# Kasli-SOC_bank502_DDR.net
KiCad netlist of a schematic drawn in Altium Designer
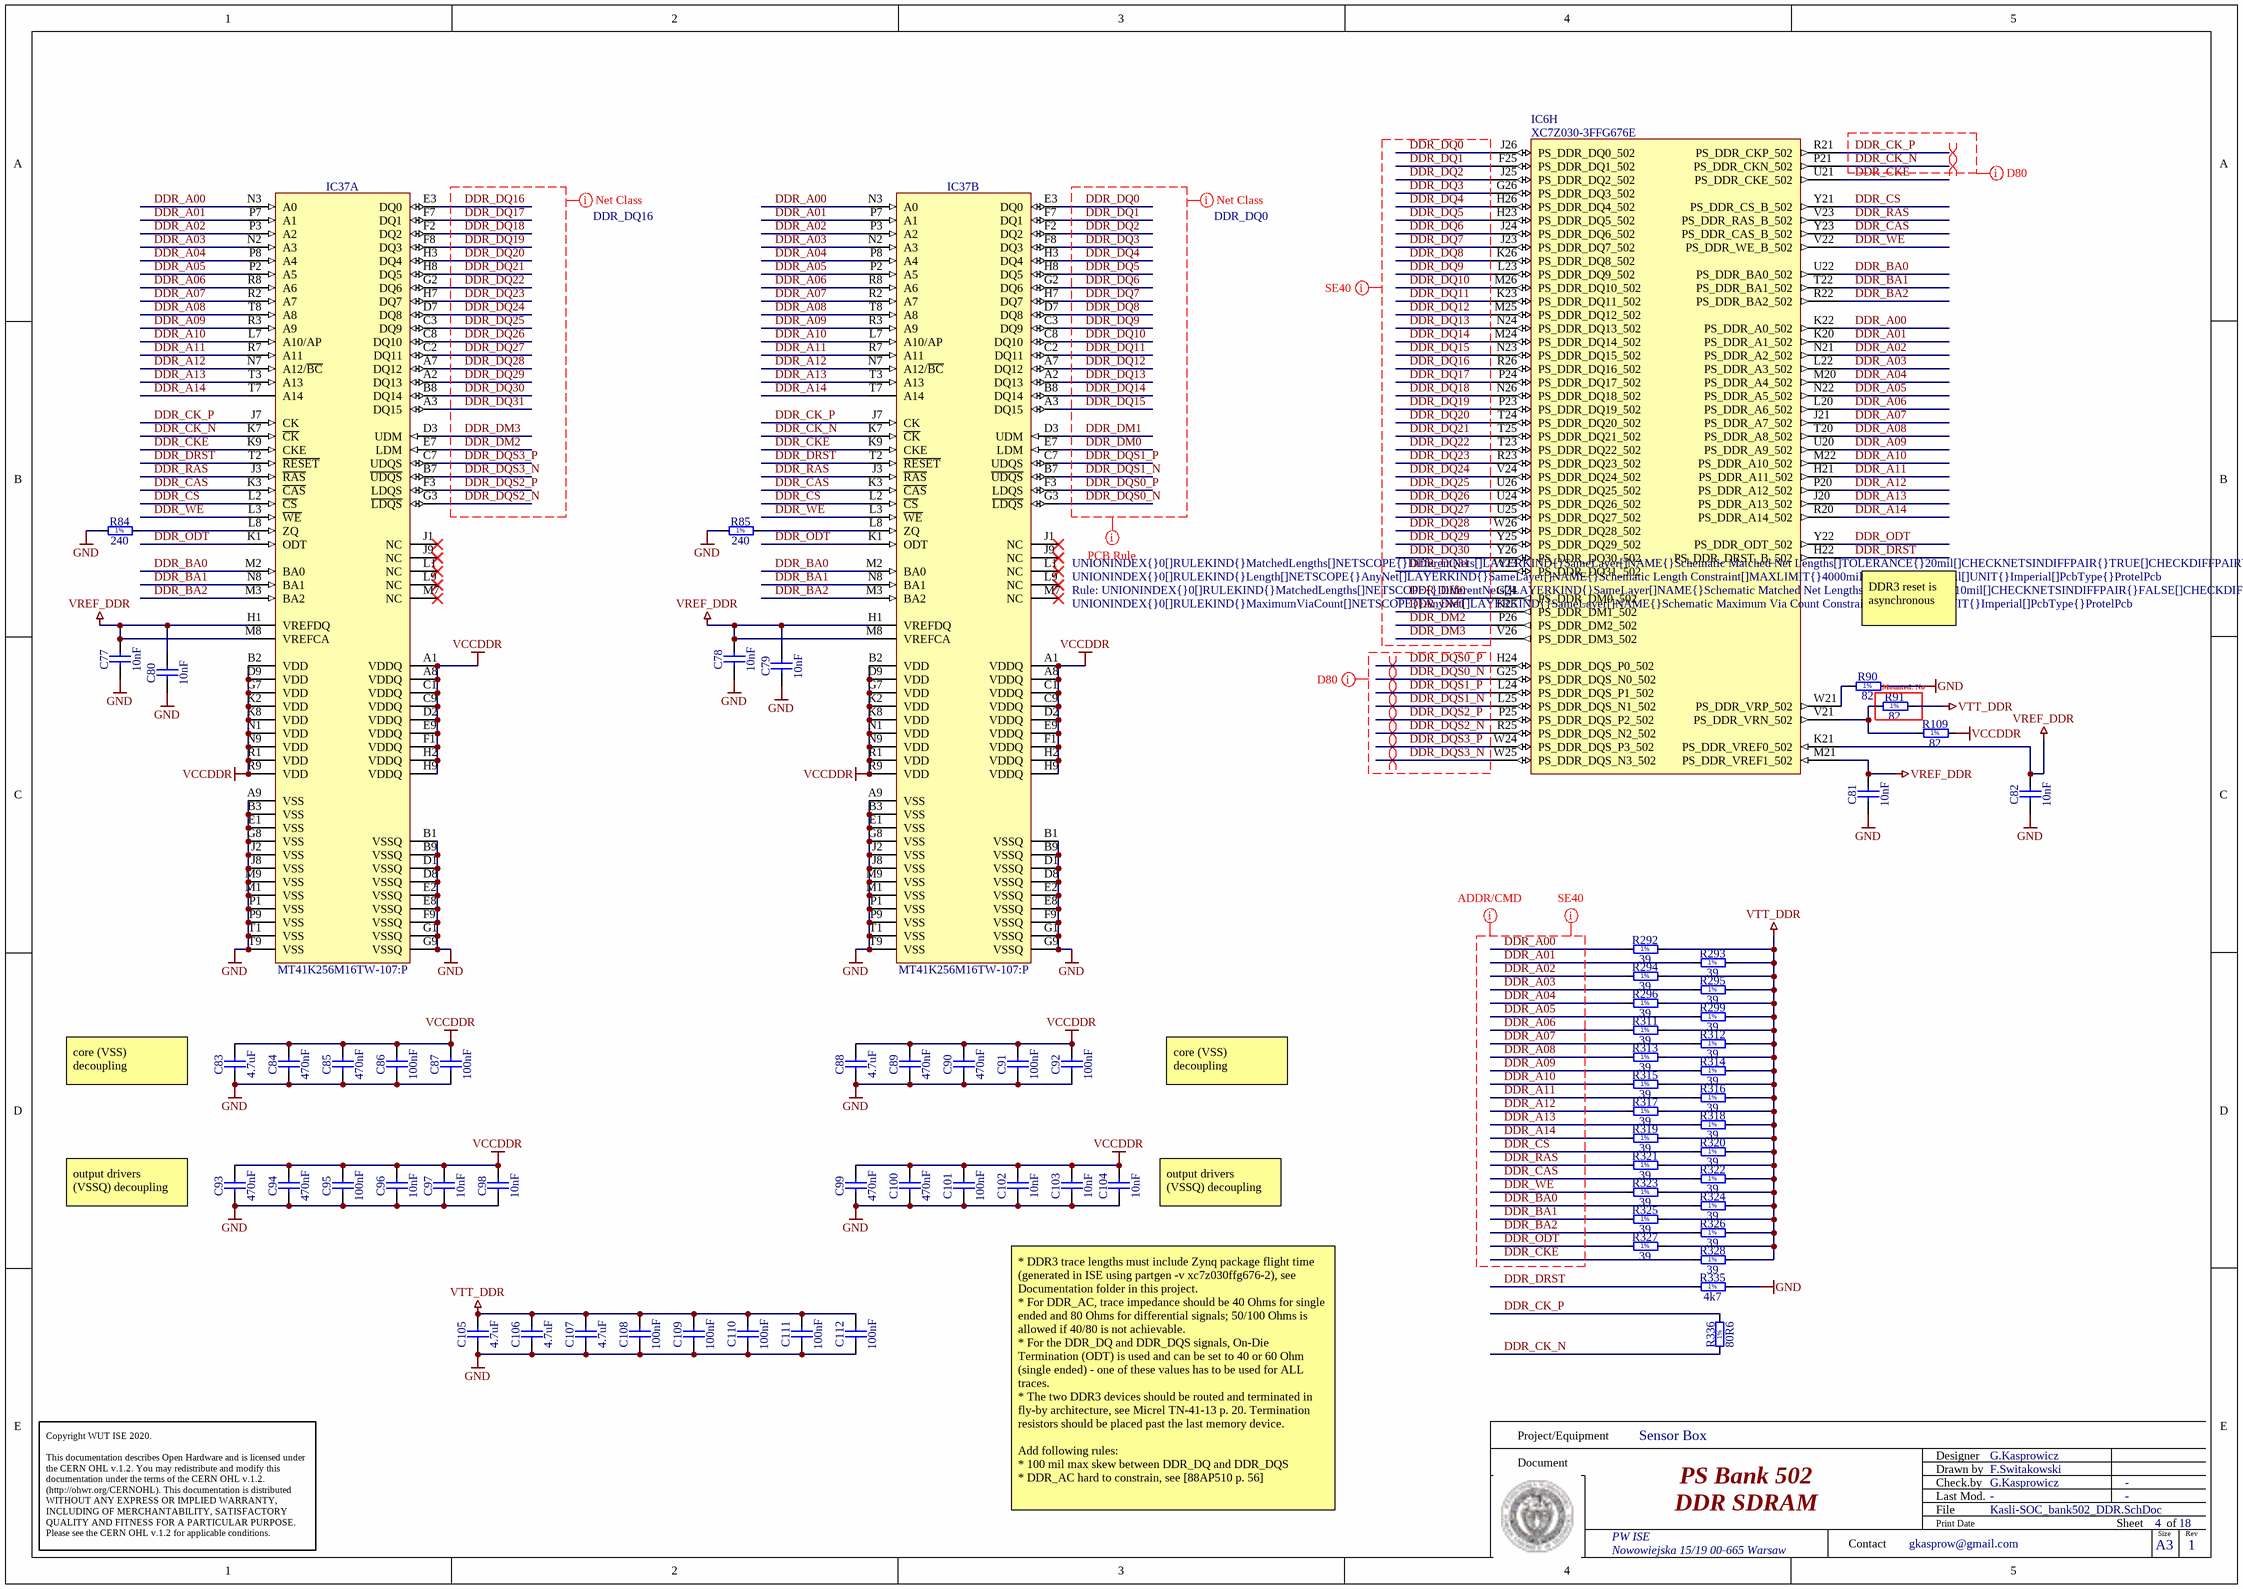
[diagram p0: Kasli-SOC_bank502_DDR.SchDoc]

(export (version "E")
  (design (tool "Eeschema 10.0.6"))
  (components
    (comp (ref "C77")
      (value "10nF")
      (footprint "CAPC1005X55N")
      (description "Non-polarised capacitor")
      (fields
        (field (name "PART NUMBER") "CC0402_10NF_16V_10%_X7R")
        (field (name "VOLTAGE") "16V")
        (field (name "AUTHOR") "CERN DEM JLC")
      )
      (libsource (lib "Capacitors") (part "Capacitor - non polarized"))
    )
    (comp (ref "C78")
      (value "10nF")
      (footprint "CAPC1005X55N")
      (description "Non-polarised capacitor")
      (fields
        (field (name "PART NUMBER") "CC0402_10NF_16V_10%_X7R")
        (field (name "VOLTAGE") "16V")
        (field (name "AUTHOR") "CERN DEM JLC")
      )
      (libsource (lib "Capacitors") (part "Capacitor - non polarized"))
    )
    (comp (ref "C79")
      (value "10nF")
      (footprint "CAPC1005X55N")
      (description "Non-polarised capacitor")
      (fields
        (field (name "PART NUMBER") "CC0402_10NF_16V_10%_X7R")
        (field (name "VOLTAGE") "16V")
        (field (name "AUTHOR") "CERN DEM JLC")
      )
      (libsource (lib "Capacitors") (part "Capacitor - non polarized"))
    )
    (comp (ref "C80")
      (value "10nF")
      (footprint "CAPC1005X55N")
      (description "Non-polarised capacitor")
      (fields
        (field (name "PART NUMBER") "CC0402_10NF_16V_10%_X7R")
        (field (name "VOLTAGE") "16V")
        (field (name "AUTHOR") "CERN DEM JLC")
      )
      (libsource (lib "Capacitors") (part "Capacitor - non polarized"))
    )
    (comp (ref "C81")
      (value "10nF")
      (footprint "CAPC0603X33N")
      (description "Non-polarised capacitor")
      (fields
        (field (name "PART NUMBER") "CC0201_10NF_10V_10%_X5R")
        (field (name "VOLTAGE") "10V")
        (field (name "AUTHOR") "CERN DEM JLC")
      )
      (libsource (lib "Capacitors") (part "Capacitor - non polarized"))
    )
    (comp (ref "C82")
      (value "10nF")
      (footprint "CAPC0603X33N")
      (description "Non-polarised capacitor")
      (fields
        (field (name "PART NUMBER") "CC0201_10NF_10V_10%_X5R")
        (field (name "VOLTAGE") "10V")
        (field (name "AUTHOR") "CERN DEM JLC")
      )
      (libsource (lib "Capacitors") (part "Capacitor - non polarized"))
    )
    (comp (ref "C83")
      (value "4.7uF")
      (footprint "CAPC1005X55N")
      (description "Non-polarised capacitor")
      (fields
        (field (name "PART NUMBER") "CC0402_4.7UF_6.3V_20%_X5R")
        (field (name "VOLTAGE") "6.3V")
        (field (name "AUTHOR") "CERN DEM JLC")
      )
      (libsource (lib "Capacitors") (part "Capacitor - non polarized"))
    )
    (comp (ref "C84")
      (value "470nF")
      (footprint "CAPC1005X55N")
      (description "Non-polarised capacitor")
      (fields
        (field (name "PART NUMBER") "CC0402_470NF_16V_10%_X5R")
        (field (name "VOLTAGE") "16V")
        (field (name "AUTHOR") "CERN DEM JLC")
      )
      (libsource (lib "Capacitors") (part "Capacitor - non polarized"))
    )
    (comp (ref "C85")
      (value "470nF")
      (footprint "CAPC1005X55N")
      (description "Non-polarised capacitor")
      (fields
        (field (name "PART NUMBER") "CC0402_470NF_16V_10%_X5R")
        (field (name "VOLTAGE") "16V")
        (field (name "AUTHOR") "CERN DEM JLC")
      )
      (libsource (lib "Capacitors") (part "Capacitor - non polarized"))
    )
    (comp (ref "C86")
      (value "100nF")
      (footprint "CAPC1005X55N")
      (description "Non-polarised capacitor")
      (fields
        (field (name "PART NUMBER") "CC0402_100NF_16V_10%_X7R")
        (field (name "VOLTAGE") "16V")
        (field (name "AUTHOR") "CERN DEM JLC")
      )
      (libsource (lib "Capacitors") (part "Capacitor - non polarized"))
    )
    (comp (ref "C87")
      (value "100nF")
      (footprint "CAPC1005X55N")
      (description "Non-polarised capacitor")
      (fields
        (field (name "PART NUMBER") "CC0402_100NF_16V_10%_X7R")
        (field (name "VOLTAGE") "16V")
        (field (name "AUTHOR") "CERN DEM JLC")
      )
      (libsource (lib "Capacitors") (part "Capacitor - non polarized"))
    )
    (comp (ref "C88")
      (value "4.7uF")
      (footprint "CAPC1005X55N")
      (description "Non-polarised capacitor")
      (fields
        (field (name "PART NUMBER") "CC0402_4.7UF_6.3V_20%_X5R")
        (field (name "VOLTAGE") "6.3V")
        (field (name "AUTHOR") "CERN DEM JLC")
      )
      (libsource (lib "Capacitors") (part "Capacitor - non polarized"))
    )
    (comp (ref "C89")
      (value "470nF")
      (footprint "CAPC1005X55N")
      (description "Non-polarised capacitor")
      (fields
        (field (name "PART NUMBER") "CC0402_470NF_16V_10%_X5R")
        (field (name "VOLTAGE") "16V")
        (field (name "AUTHOR") "CERN DEM JLC")
      )
      (libsource (lib "Capacitors") (part "Capacitor - non polarized"))
    )
    (comp (ref "C90")
      (value "470nF")
      (footprint "CAPC1005X55N")
      (description "Non-polarised capacitor")
      (fields
        (field (name "PART NUMBER") "CC0402_470NF_16V_10%_X5R")
        (field (name "VOLTAGE") "16V")
        (field (name "AUTHOR") "CERN DEM JLC")
      )
      (libsource (lib "Capacitors") (part "Capacitor - non polarized"))
    )
    (comp (ref "C91")
      (value "100nF")
      (footprint "CAPC1005X55N")
      (description "Non-polarised capacitor")
      (fields
        (field (name "PART NUMBER") "CC0402_100NF_16V_10%_X7R")
        (field (name "VOLTAGE") "16V")
        (field (name "AUTHOR") "CERN DEM JLC")
      )
      (libsource (lib "Capacitors") (part "Capacitor - non polarized"))
    )
    (comp (ref "C92")
      (value "100nF")
      (footprint "CAPC1005X55N")
      (description "Non-polarised capacitor")
      (fields
        (field (name "PART NUMBER") "CC0402_100NF_16V_10%_X7R")
        (field (name "VOLTAGE") "16V")
        (field (name "AUTHOR") "CERN DEM JLC")
      )
      (libsource (lib "Capacitors") (part "Capacitor - non polarized"))
    )
    (comp (ref "C93")
      (value "470nF")
      (footprint "CAPC1005X55N")
      (description "Non-polarised capacitor")
      (fields
        (field (name "PART NUMBER") "CC0402_470NF_16V_10%_X5R")
        (field (name "VOLTAGE") "16V")
        (field (name "AUTHOR") "CERN DEM JLC")
      )
      (libsource (lib "Capacitors") (part "Capacitor - non polarized"))
    )
    (comp (ref "C94")
      (value "470nF")
      (footprint "CAPC1005X55N")
      (description "Non-polarised capacitor")
      (fields
        (field (name "PART NUMBER") "CC0402_470NF_16V_10%_X5R")
        (field (name "VOLTAGE") "16V")
        (field (name "AUTHOR") "CERN DEM JLC")
      )
      (libsource (lib "Capacitors") (part "Capacitor - non polarized"))
    )
    (comp (ref "C95")
      (value "100nF")
      (footprint "CAPC1005X55N")
      (description "Non-polarised capacitor")
      (fields
        (field (name "PART NUMBER") "CC0402_100NF_16V_10%_X7R")
        (field (name "VOLTAGE") "16V")
        (field (name "AUTHOR") "CERN DEM JLC")
      )
      (libsource (lib "Capacitors") (part "Capacitor - non polarized"))
    )
    (comp (ref "C96")
      (value "10nF")
      (footprint "CAPC1005X55N")
      (description "Non-polarised capacitor")
      (fields
        (field (name "PART NUMBER") "CC0402_10NF_16V_10%_X7R")
        (field (name "VOLTAGE") "16V")
        (field (name "AUTHOR") "CERN DEM JLC")
      )
      (libsource (lib "Capacitors") (part "Capacitor - non polarized"))
    )
    (comp (ref "C97")
      (value "10nF")
      (footprint "CAPC1005X55N")
      (description "Non-polarised capacitor")
      (fields
        (field (name "PART NUMBER") "CC0402_10NF_16V_10%_X7R")
        (field (name "VOLTAGE") "16V")
        (field (name "AUTHOR") "CERN DEM JLC")
      )
      (libsource (lib "Capacitors") (part "Capacitor - non polarized"))
    )
    (comp (ref "C98")
      (value "10nF")
      (footprint "CAPC1005X55N")
      (description "Non-polarised capacitor")
      (fields
        (field (name "PART NUMBER") "CC0402_10NF_16V_10%_X7R")
        (field (name "VOLTAGE") "16V")
        (field (name "AUTHOR") "CERN DEM JLC")
      )
      (libsource (lib "Capacitors") (part "Capacitor - non polarized"))
    )
    (comp (ref "C99")
      (value "470nF")
      (footprint "CAPC1005X55N")
      (description "Non-polarised capacitor")
      (fields
        (field (name "PART NUMBER") "CC0402_470NF_16V_10%_X5R")
        (field (name "VOLTAGE") "16V")
        (field (name "AUTHOR") "CERN DEM JLC")
      )
      (libsource (lib "Capacitors") (part "Capacitor - non polarized"))
    )
    (comp (ref "C100")
      (value "470nF")
      (footprint "CAPC1005X55N")
      (description "Non-polarised capacitor")
      (fields
        (field (name "PART NUMBER") "CC0402_470NF_16V_10%_X5R")
        (field (name "VOLTAGE") "16V")
        (field (name "AUTHOR") "CERN DEM JLC")
      )
      (libsource (lib "Capacitors") (part "Capacitor - non polarized"))
    )
    (comp (ref "C101")
      (value "100nF")
      (footprint "CAPC1005X55N")
      (description "Non-polarised capacitor")
      (fields
        (field (name "PART NUMBER") "CC0402_100NF_16V_10%_X7R")
        (field (name "VOLTAGE") "16V")
        (field (name "AUTHOR") "CERN DEM JLC")
      )
      (libsource (lib "Capacitors") (part "Capacitor - non polarized"))
    )
    (comp (ref "C102")
      (value "10nF")
      (footprint "CAPC1005X55N")
      (description "Non-polarised capacitor")
      (fields
        (field (name "PART NUMBER") "CC0402_10NF_16V_10%_X7R")
        (field (name "VOLTAGE") "16V")
        (field (name "AUTHOR") "CERN DEM JLC")
      )
      (libsource (lib "Capacitors") (part "Capacitor - non polarized"))
    )
    (comp (ref "C103")
      (value "10nF")
      (footprint "CAPC1005X55N")
      (description "Non-polarised capacitor")
      (fields
        (field (name "PART NUMBER") "CC0402_10NF_16V_10%_X7R")
        (field (name "VOLTAGE") "16V")
        (field (name "AUTHOR") "CERN DEM JLC")
      )
      (libsource (lib "Capacitors") (part "Capacitor - non polarized"))
    )
    (comp (ref "C104")
      (value "10nF")
      (footprint "CAPC1005X55N")
      (description "Non-polarised capacitor")
      (fields
        (field (name "PART NUMBER") "CC0402_10NF_16V_10%_X7R")
        (field (name "VOLTAGE") "16V")
        (field (name "AUTHOR") "CERN DEM JLC")
      )
      (libsource (lib "Capacitors") (part "Capacitor - non polarized"))
    )
    (comp (ref "C105")
      (value "4.7uF")
      (footprint "CAPC1005X55N")
      (description "Non-polarised capacitor")
      (fields
        (field (name "PART NUMBER") "CC0402_4.7UF_6.3V_20%_X5R")
        (field (name "VOLTAGE") "6.3V")
        (field (name "AUTHOR") "CERN DEM JLC")
      )
      (libsource (lib "Capacitors") (part "Capacitor - non polarized"))
    )
    (comp (ref "C106")
      (value "4.7uF")
      (footprint "CAPC1005X55N")
      (description "Non-polarised capacitor")
      (fields
        (field (name "PART NUMBER") "CC0402_4.7UF_6.3V_20%_X5R")
        (field (name "VOLTAGE") "6.3V")
        (field (name "AUTHOR") "CERN DEM JLC")
      )
      (libsource (lib "Capacitors") (part "Capacitor - non polarized"))
    )
    (comp (ref "C107")
      (value "4.7uF")
      (footprint "CAPC1005X55N")
      (description "Non-polarised capacitor")
      (fields
        (field (name "PART NUMBER") "CC0402_4.7UF_6.3V_20%_X5R")
        (field (name "VOLTAGE") "6.3V")
        (field (name "AUTHOR") "CERN DEM JLC")
      )
      (libsource (lib "Capacitors") (part "Capacitor - non polarized"))
    )
    (comp (ref "C108")
      (value "100nF")
      (footprint "CAPC1005X55N")
      (description "Non-polarised capacitor")
      (fields
        (field (name "PART NUMBER") "CC0402_100NF_16V_10%_X7R")
        (field (name "VOLTAGE") "16V")
        (field (name "AUTHOR") "CERN DEM JLC")
      )
      (libsource (lib "Capacitors") (part "Capacitor - non polarized"))
    )
    (comp (ref "C109")
      (value "100nF")
      (footprint "CAPC1005X55N")
      (description "Non-polarised capacitor")
      (fields
        (field (name "PART NUMBER") "CC0402_100NF_16V_10%_X7R")
        (field (name "VOLTAGE") "16V")
        (field (name "AUTHOR") "CERN DEM JLC")
      )
      (libsource (lib "Capacitors") (part "Capacitor - non polarized"))
    )
    (comp (ref "C110")
      (value "100nF")
      (footprint "CAPC1005X55N")
      (description "Non-polarised capacitor")
      (fields
        (field (name "PART NUMBER") "CC0402_100NF_16V_10%_X7R")
        (field (name "VOLTAGE") "16V")
        (field (name "AUTHOR") "CERN DEM JLC")
      )
      (libsource (lib "Capacitors") (part "Capacitor - non polarized"))
    )
    (comp (ref "C111")
      (value "100nF")
      (footprint "CAPC1005X55N")
      (description "Non-polarised capacitor")
      (fields
        (field (name "PART NUMBER") "CC0402_100NF_16V_10%_X7R")
        (field (name "VOLTAGE") "16V")
        (field (name "AUTHOR") "CERN DEM JLC")
      )
      (libsource (lib "Capacitors") (part "Capacitor - non polarized"))
    )
    (comp (ref "C112")
      (value "100nF")
      (footprint "CAPC1005X55N")
      (description "Non-polarised capacitor")
      (fields
        (field (name "PART NUMBER") "CC0402_100NF_16V_10%_X7R")
        (field (name "VOLTAGE") "16V")
        (field (name "AUTHOR") "CERN DEM JLC")
      )
      (libsource (lib "Capacitors") (part "Capacitor - non polarized"))
    )
    (comp (ref "IC6")
      (value "XC7Z030-3FFG676E")
      (footprint "BGA676C100P26X26_2700X2700X324")
      (fields (field (name "MANUFACTURER") "XILINX") (field (name "AUTHOR") "CERN DEM JLC"))
      (libsource (lib "ICs And Semiconductors") (part "XC7Z030-2FFG676I"))
    )
    (comp (ref "IC37A")
      (value "MT41K256M16TW-107:P")
      (footprint "BGA96C80P9X16_800X1400X120")
      (description "32 Meg x 16 x 8 Banks DDR3L SDRAM")
      (fields (field (name "MANUFACTURER") "MICRON TECHNOLOGY") (field (name "AUTHOR") "CERN DEM MR"))
      (libsource (lib "ICs And Semiconductors") (part "MT41K256M16TW-107{colon}P"))
    )
    (comp (ref "IC37B")
      (value "MT41K256M16TW-107:P")
      (footprint "BGA96C80P9X16_800X1400X120")
      (description "32 Meg x 16 x 8 Banks DDR3L SDRAM")
      (fields (field (name "MANUFACTURER") "MICRON TECHNOLOGY") (field (name "AUTHOR") "CERN DEM MR"))
      (libsource (lib "ICs And Semiconductors") (part "MT41K256M16TW-107{colon}P"))
    )
    (comp (ref "R84")
      (value "240")
      (footprint "RESC1005X40N")
      (description "Resistor - 1%")
      (fields
        (field (name "PART NUMBER") "R0402_240R_1%_0.0625W_100PPM")
        (field (name "POWER") "0.0625W")
        (field (name "AUTHOR") "CERN DEM JLC")
      )
      (libsource (lib "Resistors") (part "Resistor - 1%"))
    )
    (comp (ref "R85")
      (value "240")
      (footprint "RESC1005X40N")
      (description "Resistor - 1%")
      (fields
        (field (name "PART NUMBER") "R0402_240R_1%_0.0625W_100PPM")
        (field (name "POWER") "0.0625W")
        (field (name "AUTHOR") "CERN DEM JLC")
      )
      (libsource (lib "Resistors") (part "Resistor - 1%"))
    )
    (comp (ref "R90")
      (value "82")
      (footprint "RESC1005X40N")
      (description "Resistor - 1%")
      (fields
        (field (name "PART NUMBER") "R0402_82R_1%_0.0625W_100PPM")
        (field (name "POWER") "0.0625W")
        (field (name "AUTHOR") "CERN DEM JLC")
      )
      (libsource (lib "Resistors") (part "Resistor - 1%"))
    )
    (comp (ref "R91")
      (value "82")
      (footprint "RESC1005X40N")
      (description "Resistor - 1%")
      (fields
        (field (name "PART NUMBER") "R0402_82R_1%_0.0625W_100PPM")
        (field (name "POWER") "0.0625W")
        (field (name "AUTHOR") "CERN DEM JLC")
      )
      (libsource (lib "Resistors") (part "Resistor - 1%"))
    )
    (comp (ref "R109")
      (value "82")
      (footprint "RESC1005X40N")
      (description "Resistor - 1%")
      (fields
        (field (name "PART NUMBER") "R0402_82R_1%_0.0625W_100PPM")
        (field (name "POWER") "0.0625W")
        (field (name "AUTHOR") "CERN DEM JLC")
      )
      (libsource (lib "Resistors") (part "Resistor - 1%"))
    )
    (comp (ref "R292")
      (value "39")
      (footprint "RESC1005X40N")
      (description "Resistor - 1%")
      (fields
        (field (name "PART NUMBER") "R0402_39R_1%_0.0625W_100PPM")
        (field (name "POWER") "0.0625W")
        (field (name "AUTHOR") "CERN DEM JLC")
      )
      (libsource (lib "Resistors") (part "Resistor - 1%"))
    )
    (comp (ref "R293")
      (value "39")
      (footprint "RESC1005X40N")
      (description "Resistor - 1%")
      (fields
        (field (name "PART NUMBER") "R0402_39R_1%_0.0625W_100PPM")
        (field (name "POWER") "0.0625W")
        (field (name "AUTHOR") "CERN DEM JLC")
      )
      (libsource (lib "Resistors") (part "Resistor - 1%"))
    )
    (comp (ref "R294")
      (value "39")
      (footprint "RESC1005X40N")
      (description "Resistor - 1%")
      (fields
        (field (name "PART NUMBER") "R0402_39R_1%_0.0625W_100PPM")
        (field (name "POWER") "0.0625W")
        (field (name "AUTHOR") "CERN DEM JLC")
      )
      (libsource (lib "Resistors") (part "Resistor - 1%"))
    )
    (comp (ref "R295")
      (value "39")
      (footprint "RESC1005X40N")
      (description "Resistor - 1%")
      (fields
        (field (name "PART NUMBER") "R0402_39R_1%_0.0625W_100PPM")
        (field (name "POWER") "0.0625W")
        (field (name "AUTHOR") "CERN DEM JLC")
      )
      (libsource (lib "Resistors") (part "Resistor - 1%"))
    )
    (comp (ref "R296")
      (value "39")
      (footprint "RESC1005X40N")
      (description "Resistor - 1%")
      (fields
        (field (name "PART NUMBER") "R0402_39R_1%_0.0625W_100PPM")
        (field (name "POWER") "0.0625W")
        (field (name "AUTHOR") "CERN DEM JLC")
      )
      (libsource (lib "Resistors") (part "Resistor - 1%"))
    )
    (comp (ref "R299")
      (value "39")
      (footprint "RESC1005X40N")
      (description "Resistor - 1%")
      (fields
        (field (name "PART NUMBER") "R0402_39R_1%_0.0625W_100PPM")
        (field (name "POWER") "0.0625W")
        (field (name "AUTHOR") "CERN DEM JLC")
      )
      (libsource (lib "Resistors") (part "Resistor - 1%"))
    )
    (comp (ref "R311")
      (value "39")
      (footprint "RESC1005X40N")
      (description "Resistor - 1%")
      (fields
        (field (name "PART NUMBER") "R0402_39R_1%_0.0625W_100PPM")
        (field (name "POWER") "0.0625W")
        (field (name "AUTHOR") "CERN DEM JLC")
      )
      (libsource (lib "Resistors") (part "Resistor - 1%"))
    )
    (comp (ref "R312")
      (value "39")
      (footprint "RESC1005X40N")
      (description "Resistor - 1%")
      (fields
        (field (name "PART NUMBER") "R0402_39R_1%_0.0625W_100PPM")
        (field (name "POWER") "0.0625W")
        (field (name "AUTHOR") "CERN DEM JLC")
      )
      (libsource (lib "Resistors") (part "Resistor - 1%"))
    )
    (comp (ref "R313")
      (value "39")
      (footprint "RESC1005X40N")
      (description "Resistor - 1%")
      (fields
        (field (name "PART NUMBER") "R0402_39R_1%_0.0625W_100PPM")
        (field (name "POWER") "0.0625W")
        (field (name "AUTHOR") "CERN DEM JLC")
      )
      (libsource (lib "Resistors") (part "Resistor - 1%"))
    )
    (comp (ref "R314")
      (value "39")
      (footprint "RESC1005X40N")
      (description "Resistor - 1%")
      (fields
        (field (name "PART NUMBER") "R0402_39R_1%_0.0625W_100PPM")
        (field (name "POWER") "0.0625W")
        (field (name "AUTHOR") "CERN DEM JLC")
      )
      (libsource (lib "Resistors") (part "Resistor - 1%"))
    )
    (comp (ref "R315")
      (value "39")
      (footprint "RESC1005X40N")
      (description "Resistor - 1%")
      (fields
        (field (name "PART NUMBER") "R0402_39R_1%_0.0625W_100PPM")
        (field (name "POWER") "0.0625W")
        (field (name "AUTHOR") "CERN DEM JLC")
      )
      (libsource (lib "Resistors") (part "Resistor - 1%"))
    )
    (comp (ref "R316")
      (value "39")
      (footprint "RESC1005X40N")
      (description "Resistor - 1%")
      (fields
        (field (name "PART NUMBER") "R0402_39R_1%_0.0625W_100PPM")
        (field (name "POWER") "0.0625W")
        (field (name "AUTHOR") "CERN DEM JLC")
      )
      (libsource (lib "Resistors") (part "Resistor - 1%"))
    )
    (comp (ref "R317")
      (value "39")
      (footprint "RESC1005X40N")
      (description "Resistor - 1%")
      (fields
        (field (name "PART NUMBER") "R0402_39R_1%_0.0625W_100PPM")
        (field (name "POWER") "0.0625W")
        (field (name "AUTHOR") "CERN DEM JLC")
      )
      (libsource (lib "Resistors") (part "Resistor - 1%"))
    )
    (comp (ref "R318")
      (value "39")
      (footprint "RESC1005X40N")
      (description "Resistor - 1%")
      (fields
        (field (name "PART NUMBER") "R0402_39R_1%_0.0625W_100PPM")
        (field (name "POWER") "0.0625W")
        (field (name "AUTHOR") "CERN DEM JLC")
      )
      (libsource (lib "Resistors") (part "Resistor - 1%"))
    )
    (comp (ref "R319")
      (value "39")
      (footprint "RESC1005X40N")
      (description "Resistor - 1%")
      (fields
        (field (name "PART NUMBER") "R0402_39R_1%_0.0625W_100PPM")
        (field (name "POWER") "0.0625W")
        (field (name "AUTHOR") "CERN DEM JLC")
      )
      (libsource (lib "Resistors") (part "Resistor - 1%"))
    )
    (comp (ref "R320")
      (value "39")
      (footprint "RESC1005X40N")
      (description "Resistor - 1%")
      (fields
        (field (name "PART NUMBER") "R0402_39R_1%_0.0625W_100PPM")
        (field (name "POWER") "0.0625W")
        (field (name "AUTHOR") "CERN DEM JLC")
      )
      (libsource (lib "Resistors") (part "Resistor - 1%"))
    )
    (comp (ref "R321")
      (value "39")
      (footprint "RESC1005X40N")
      (description "Resistor - 1%")
      (fields
        (field (name "PART NUMBER") "R0402_39R_1%_0.0625W_100PPM")
        (field (name "POWER") "0.0625W")
        (field (name "AUTHOR") "CERN DEM JLC")
      )
      (libsource (lib "Resistors") (part "Resistor - 1%"))
    )
    (comp (ref "R322")
      (value "39")
      (footprint "RESC1005X40N")
      (description "Resistor - 1%")
      (fields
        (field (name "PART NUMBER") "R0402_39R_1%_0.0625W_100PPM")
        (field (name "POWER") "0.0625W")
        (field (name "AUTHOR") "CERN DEM JLC")
      )
      (libsource (lib "Resistors") (part "Resistor - 1%"))
    )
    (comp (ref "R323")
      (value "39")
      (footprint "RESC1005X40N")
      (description "Resistor - 1%")
      (fields
        (field (name "PART NUMBER") "R0402_39R_1%_0.0625W_100PPM")
        (field (name "POWER") "0.0625W")
        (field (name "AUTHOR") "CERN DEM JLC")
      )
      (libsource (lib "Resistors") (part "Resistor - 1%"))
    )
    (comp (ref "R324")
      (value "39")
      (footprint "RESC1005X40N")
      (description "Resistor - 1%")
      (fields
        (field (name "PART NUMBER") "R0402_39R_1%_0.0625W_100PPM")
        (field (name "POWER") "0.0625W")
        (field (name "AUTHOR") "CERN DEM JLC")
      )
      (libsource (lib "Resistors") (part "Resistor - 1%"))
    )
    (comp (ref "R325")
      (value "39")
      (footprint "RESC1005X40N")
      (description "Resistor - 1%")
      (fields
        (field (name "PART NUMBER") "R0402_39R_1%_0.0625W_100PPM")
        (field (name "POWER") "0.0625W")
        (field (name "AUTHOR") "CERN DEM JLC")
      )
      (libsource (lib "Resistors") (part "Resistor - 1%"))
    )
    (comp (ref "R326")
      (value "39")
      (footprint "RESC1005X40N")
      (description "Resistor - 1%")
      (fields
        (field (name "PART NUMBER") "R0402_39R_1%_0.0625W_100PPM")
        (field (name "POWER") "0.0625W")
        (field (name "AUTHOR") "CERN DEM JLC")
      )
      (libsource (lib "Resistors") (part "Resistor - 1%"))
    )
    (comp (ref "R327")
      (value "39")
      (footprint "RESC1005X40N")
      (description "Resistor - 1%")
      (fields
        (field (name "PART NUMBER") "R0402_39R_1%_0.0625W_100PPM")
        (field (name "POWER") "0.0625W")
        (field (name "AUTHOR") "CERN DEM JLC")
      )
      (libsource (lib "Resistors") (part "Resistor - 1%"))
    )
    (comp (ref "R328")
      (value "39")
      (footprint "RESC1005X40N")
      (description "Resistor - 1%")
      (fields
        (field (name "PART NUMBER") "R0402_39R_1%_0.0625W_100PPM")
        (field (name "POWER") "0.0625W")
        (field (name "AUTHOR") "CERN DEM JLC")
      )
      (libsource (lib "Resistors") (part "Resistor - 1%"))
    )
    (comp (ref "R335")
      (value "4k7")
      (footprint "RESC1005X40N")
      (description "Resistor - 1%")
      (fields
        (field (name "PART NUMBER") "R0402_4K7_1%_0.0625W_100PPM")
        (field (name "POWER") "0.0625W")
        (field (name "AUTHOR") "CERN DEM JLC")
      )
      (libsource (lib "Resistors") (part "Resistor - 1%"))
    )
    (comp (ref "R336")
      (value "80R6")
      (footprint "RESC1005X40N")
      (description "Resistor - 1%")
      (fields
        (field (name "PART NUMBER") "R0402_80R6_1%_0.1W_100PPM")
        (field (name "POWER") "0.1W")
        (field (name "AUTHOR") "CERN DEM JLC")
      )
      (libsource (lib "Resistors") (part "Resistor - 1%"))
    )
  )
  (nets
    (net (code "1") (name "/DDR_A00") (class "Default")
      (node (ref "IC37A") (pin "N3") (pinfunction "A0_N3") (pintype "input"))
      (node (ref "IC37B") (pin "N3") (pinfunction "A0_N3") (pintype "input"))
      (node (ref "IC6") (pin "K22") (pinfunction "PS_DDR_A0_502_K22") (pintype "output"))
      (node (ref "R292") (pin "1") (pinfunction "1_1") (pintype "passive"))
    )
    (net (code "2") (name "/DDR_A01") (class "Default")
      (node (ref "IC37A") (pin "P7") (pinfunction "A1_P7") (pintype "input"))
      (node (ref "IC37B") (pin "P7") (pinfunction "A1_P7") (pintype "input"))
      (node (ref "IC6") (pin "K20") (pinfunction "PS_DDR_A1_502_K20") (pintype "output"))
      (node (ref "R293") (pin "1") (pinfunction "1_1") (pintype "passive"))
    )
    (net (code "3") (name "/DDR_A02") (class "Default")
      (node (ref "IC37A") (pin "P3") (pinfunction "A2_P3") (pintype "input"))
      (node (ref "IC37B") (pin "P3") (pinfunction "A2_P3") (pintype "input"))
      (node (ref "IC6") (pin "N21") (pinfunction "PS_DDR_A2_502_N21") (pintype "output"))
      (node (ref "R294") (pin "1") (pinfunction "1_1") (pintype "passive"))
    )
    (net (code "4") (name "/DDR_A03") (class "Default")
      (node (ref "IC37A") (pin "N2") (pinfunction "A3_N2") (pintype "input"))
      (node (ref "IC37B") (pin "N2") (pinfunction "A3_N2") (pintype "input"))
      (node (ref "IC6") (pin "L22") (pinfunction "PS_DDR_A3_502_L22") (pintype "output"))
      (node (ref "R295") (pin "1") (pinfunction "1_1") (pintype "passive"))
    )
    (net (code "5") (name "/DDR_A04") (class "Default")
      (node (ref "IC37A") (pin "P8") (pinfunction "A4_P8") (pintype "input"))
      (node (ref "IC37B") (pin "P8") (pinfunction "A4_P8") (pintype "input"))
      (node (ref "IC6") (pin "M20") (pinfunction "PS_DDR_A4_502_M20") (pintype "output"))
      (node (ref "R296") (pin "1") (pinfunction "1_1") (pintype "passive"))
    )
    (net (code "6") (name "/DDR_A05") (class "Default")
      (node (ref "IC37A") (pin "P2") (pinfunction "A5_P2") (pintype "input"))
      (node (ref "IC37B") (pin "P2") (pinfunction "A5_P2") (pintype "input"))
      (node (ref "IC6") (pin "N22") (pinfunction "PS_DDR_A5_502_N22") (pintype "output"))
      (node (ref "R299") (pin "1") (pinfunction "1_1") (pintype "passive"))
    )
    (net (code "7") (name "/DDR_A06") (class "Default")
      (node (ref "IC37A") (pin "R8") (pinfunction "A6_R8") (pintype "input"))
      (node (ref "IC37B") (pin "R8") (pinfunction "A6_R8") (pintype "input"))
      (node (ref "IC6") (pin "L20") (pinfunction "PS_DDR_A6_502_L20") (pintype "output"))
      (node (ref "R311") (pin "1") (pinfunction "1_1") (pintype "passive"))
    )
    (net (code "8") (name "/DDR_A07") (class "Default")
      (node (ref "IC37A") (pin "R2") (pinfunction "A7_R2") (pintype "input"))
      (node (ref "IC37B") (pin "R2") (pinfunction "A7_R2") (pintype "input"))
      (node (ref "IC6") (pin "J21") (pinfunction "PS_DDR_A7_502_J21") (pintype "output"))
      (node (ref "R312") (pin "1") (pinfunction "1_1") (pintype "passive"))
    )
    (net (code "9") (name "/DDR_A08") (class "Default")
      (node (ref "IC37A") (pin "T8") (pinfunction "A8_T8") (pintype "input"))
      (node (ref "IC37B") (pin "T8") (pinfunction "A8_T8") (pintype "input"))
      (node (ref "IC6") (pin "T20") (pinfunction "PS_DDR_A8_502_T20") (pintype "output"))
      (node (ref "R313") (pin "1") (pinfunction "1_1") (pintype "passive"))
    )
    (net (code "10") (name "/DDR_A09") (class "Default")
      (node (ref "IC37A") (pin "R3") (pinfunction "A9_R3") (pintype "input"))
      (node (ref "IC37B") (pin "R3") (pinfunction "A9_R3") (pintype "input"))
      (node (ref "IC6") (pin "U20") (pinfunction "PS_DDR_A9_502_U20") (pintype "output"))
      (node (ref "R314") (pin "1") (pinfunction "1_1") (pintype "passive"))
    )
    (net (code "11") (name "/DDR_A10") (class "Default")
      (node (ref "IC37A") (pin "L7") (pinfunction "A10/AP_L7") (pintype "input"))
      (node (ref "IC37B") (pin "L7") (pinfunction "A10/AP_L7") (pintype "input"))
      (node (ref "IC6") (pin "M22") (pinfunction "PS_DDR_A10_502_M22") (pintype "output"))
      (node (ref "R315") (pin "1") (pinfunction "1_1") (pintype "passive"))
    )
    (net (code "12") (name "/DDR_A11") (class "Default")
      (node (ref "IC37A") (pin "R7") (pinfunction "A11_R7") (pintype "input"))
      (node (ref "IC37B") (pin "R7") (pinfunction "A11_R7") (pintype "input"))
      (node (ref "IC6") (pin "H21") (pinfunction "PS_DDR_A11_502_H21") (pintype "output"))
      (node (ref "R316") (pin "1") (pinfunction "1_1") (pintype "passive"))
    )
    (net (code "13") (name "/DDR_A12") (class "Default")
      (node (ref "IC37A") (pin "N7") (pinfunction "A12/~{BC}_N7") (pintype "input"))
      (node (ref "IC37B") (pin "N7") (pinfunction "A12/~{BC}_N7") (pintype "input"))
      (node (ref "IC6") (pin "P20") (pinfunction "PS_DDR_A12_502_P20") (pintype "output"))
      (node (ref "R317") (pin "1") (pinfunction "1_1") (pintype "passive"))
    )
    (net (code "14") (name "/DDR_A13") (class "Default")
      (node (ref "IC37A") (pin "T3") (pinfunction "A13_T3") (pintype "input"))
      (node (ref "IC37B") (pin "T3") (pinfunction "A13_T3") (pintype "input"))
      (node (ref "IC6") (pin "J20") (pinfunction "PS_DDR_A13_502_J20") (pintype "output"))
      (node (ref "R318") (pin "1") (pinfunction "1_1") (pintype "passive"))
    )
    (net (code "15") (name "/DDR_A14") (class "Default")
      (node (ref "IC37A") (pin "T7") (pinfunction "A14_T7") (pintype "passive"))
      (node (ref "IC37B") (pin "T7") (pinfunction "A14_T7") (pintype "passive"))
      (node (ref "IC6") (pin "R20") (pinfunction "PS_DDR_A14_502_R20") (pintype "output"))
      (node (ref "R319") (pin "1") (pinfunction "1_1") (pintype "passive"))
    )
    (net (code "16") (name "/DDR_BA0") (class "Default")
      (node (ref "IC37A") (pin "M2") (pinfunction "BA0_M2") (pintype "input"))
      (node (ref "IC37B") (pin "M2") (pinfunction "BA0_M2") (pintype "input"))
      (node (ref "IC6") (pin "U22") (pinfunction "PS_DDR_BA0_502_U22") (pintype "output"))
      (node (ref "R324") (pin "1") (pinfunction "1_1") (pintype "passive"))
    )
    (net (code "17") (name "/DDR_BA1") (class "Default")
      (node (ref "IC37A") (pin "N8") (pinfunction "BA1_N8") (pintype "input"))
      (node (ref "IC37B") (pin "N8") (pinfunction "BA1_N8") (pintype "input"))
      (node (ref "IC6") (pin "T22") (pinfunction "PS_DDR_BA1_502_T22") (pintype "output"))
      (node (ref "R325") (pin "1") (pinfunction "1_1") (pintype "passive"))
    )
    (net (code "18") (name "/DDR_BA2") (class "Default")
      (node (ref "IC37A") (pin "M3") (pinfunction "BA2_M3") (pintype "input"))
      (node (ref "IC37B") (pin "M3") (pinfunction "BA2_M3") (pintype "input"))
      (node (ref "IC6") (pin "R22") (pinfunction "PS_DDR_BA2_502_R22") (pintype "output"))
      (node (ref "R326") (pin "1") (pinfunction "1_1") (pintype "passive"))
    )
    (net (code "19") (name "/DDR_CAS") (class "Default")
      (node (ref "IC37A") (pin "K3") (pinfunction "~{CAS}_K3") (pintype "input"))
      (node (ref "IC37B") (pin "K3") (pinfunction "~{CAS}_K3") (pintype "input"))
      (node (ref "IC6") (pin "Y23") (pinfunction "PS_DDR_CAS_B_502_Y23") (pintype "output"))
      (node (ref "R322") (pin "1") (pinfunction "1_1") (pintype "passive"))
    )
    (net (code "20") (name "/DDR_CKE") (class "Default")
      (node (ref "IC37A") (pin "K9") (pinfunction "CKE_K9") (pintype "input"))
      (node (ref "IC37B") (pin "K9") (pinfunction "CKE_K9") (pintype "input"))
      (node (ref "IC6") (pin "U21") (pinfunction "PS_DDR_CKE_502_U21") (pintype "output"))
      (node (ref "R328") (pin "1") (pinfunction "1_1") (pintype "passive"))
    )
    (net (code "21") (name "/DDR_CK_N") (class "Default")
      (node (ref "IC37A") (pin "K7") (pinfunction "~{CK}_K7") (pintype "input"))
      (node (ref "IC37B") (pin "K7") (pinfunction "~{CK}_K7") (pintype "input"))
      (node (ref "IC6") (pin "P21") (pinfunction "PS_DDR_CKN_502_P21") (pintype "output"))
      (node (ref "R336") (pin "1") (pinfunction "1_1") (pintype "passive"))
    )
    (net (code "22") (name "/DDR_CK_P") (class "Default")
      (node (ref "IC37A") (pin "J7") (pinfunction "CK_J7") (pintype "input"))
      (node (ref "IC37B") (pin "J7") (pinfunction "CK_J7") (pintype "input"))
      (node (ref "IC6") (pin "R21") (pinfunction "PS_DDR_CKP_502_R21") (pintype "output"))
      (node (ref "R336") (pin "2") (pinfunction "2_2") (pintype "passive"))
    )
    (net (code "23") (name "/DDR_CS") (class "Default")
      (node (ref "IC37A") (pin "L2") (pinfunction "~{CS}_L2") (pintype "input"))
      (node (ref "IC37B") (pin "L2") (pinfunction "~{CS}_L2") (pintype "input"))
      (node (ref "IC6") (pin "Y21") (pinfunction "PS_DDR_CS_B_502_Y21") (pintype "output"))
      (node (ref "R320") (pin "1") (pinfunction "1_1") (pintype "passive"))
    )
    (net (code "24") (name "/DDR_DM0") (class "Default")
      (node (ref "IC37B") (pin "E7") (pinfunction "LDM_E7") (pintype "input"))
      (node (ref "IC6") (pin "G24") (pinfunction "PS_DDR_DM0_502_G24") (pintype "output"))
    )
    (net (code "25") (name "/DDR_DM1") (class "Default")
      (node (ref "IC37B") (pin "D3") (pinfunction "UDM_D3") (pintype "input"))
      (node (ref "IC6") (pin "K25") (pinfunction "PS_DDR_DM1_502_K25") (pintype "output"))
    )
    (net (code "26") (name "/DDR_DM2") (class "Default")
      (node (ref "IC37A") (pin "E7") (pinfunction "LDM_E7") (pintype "input"))
      (node (ref "IC6") (pin "P26") (pinfunction "PS_DDR_DM2_502_P26") (pintype "output"))
    )
    (net (code "27") (name "/DDR_DM3") (class "Default")
      (node (ref "IC37A") (pin "D3") (pinfunction "UDM_D3") (pintype "input"))
      (node (ref "IC6") (pin "V26") (pinfunction "PS_DDR_DM3_502_V26") (pintype "output"))
    )
    (net (code "28") (name "/DDR_DQ0") (class "Default")
      (node (ref "IC37B") (pin "E3") (pinfunction "DQ0_E3") (pintype "bidirectional"))
      (node (ref "IC6") (pin "J26") (pinfunction "PS_DDR_DQ0_502_J26") (pintype "bidirectional"))
    )
    (net (code "29") (name "/DDR_DQ1") (class "Default")
      (node (ref "IC37B") (pin "F7") (pinfunction "DQ1_F7") (pintype "bidirectional"))
      (node (ref "IC6") (pin "F25") (pinfunction "PS_DDR_DQ1_502_F25") (pintype "bidirectional"))
    )
    (net (code "30") (name "/DDR_DQ2") (class "Default")
      (node (ref "IC37B") (pin "F2") (pinfunction "DQ2_F2") (pintype "bidirectional"))
      (node (ref "IC6") (pin "J25") (pinfunction "PS_DDR_DQ2_502_J25") (pintype "bidirectional"))
    )
    (net (code "31") (name "/DDR_DQ3") (class "Default")
      (node (ref "IC37B") (pin "F8") (pinfunction "DQ3_F8") (pintype "bidirectional"))
      (node (ref "IC6") (pin "G26") (pinfunction "PS_DDR_DQ3_502_G26") (pintype "bidirectional"))
    )
    (net (code "32") (name "/DDR_DQ4") (class "Default")
      (node (ref "IC37B") (pin "H3") (pinfunction "DQ4_H3") (pintype "bidirectional"))
      (node (ref "IC6") (pin "H26") (pinfunction "PS_DDR_DQ4_502_H26") (pintype "bidirectional"))
    )
    (net (code "33") (name "/DDR_DQ5") (class "Default")
      (node (ref "IC37B") (pin "H8") (pinfunction "DQ5_H8") (pintype "bidirectional"))
      (node (ref "IC6") (pin "H23") (pinfunction "PS_DDR_DQ5_502_H23") (pintype "bidirectional"))
    )
    (net (code "34") (name "/DDR_DQ6") (class "Default")
      (node (ref "IC37B") (pin "G2") (pinfunction "DQ6_G2") (pintype "bidirectional"))
      (node (ref "IC6") (pin "J24") (pinfunction "PS_DDR_DQ6_502_J24") (pintype "bidirectional"))
    )
    (net (code "35") (name "/DDR_DQ7") (class "Default")
      (node (ref "IC37B") (pin "H7") (pinfunction "DQ7_H7") (pintype "bidirectional"))
      (node (ref "IC6") (pin "J23") (pinfunction "PS_DDR_DQ7_502_J23") (pintype "bidirectional"))
    )
    (net (code "36") (name "/DDR_DQ8") (class "Default")
      (node (ref "IC37B") (pin "D7") (pinfunction "DQ8_D7") (pintype "bidirectional"))
      (node (ref "IC6") (pin "K26") (pinfunction "PS_DDR_DQ8_502_K26") (pintype "bidirectional"))
    )
    (net (code "37") (name "/DDR_DQ9") (class "Default")
      (node (ref "IC37B") (pin "C3") (pinfunction "DQ9_C3") (pintype "bidirectional"))
      (node (ref "IC6") (pin "L23") (pinfunction "PS_DDR_DQ9_502_L23") (pintype "bidirectional"))
    )
    (net (code "38") (name "/DDR_DQ10") (class "Default")
      (node (ref "IC37B") (pin "C8") (pinfunction "DQ10_C8") (pintype "bidirectional"))
      (node (ref "IC6") (pin "M26") (pinfunction "PS_DDR_DQ10_502_M26") (pintype "bidirectional"))
    )
    (net (code "39") (name "/DDR_DQ11") (class "Default")
      (node (ref "IC37B") (pin "C2") (pinfunction "DQ11_C2") (pintype "bidirectional"))
      (node (ref "IC6") (pin "K23") (pinfunction "PS_DDR_DQ11_502_K23") (pintype "bidirectional"))
    )
    (net (code "40") (name "/DDR_DQ12") (class "Default")
      (node (ref "IC37B") (pin "A7") (pinfunction "DQ12_A7") (pintype "bidirectional"))
      (node (ref "IC6") (pin "M25") (pinfunction "PS_DDR_DQ12_502_M25") (pintype "bidirectional"))
    )
    (net (code "41") (name "/DDR_DQ13") (class "Default")
      (node (ref "IC37B") (pin "A2") (pinfunction "DQ13_A2") (pintype "bidirectional"))
      (node (ref "IC6") (pin "N24") (pinfunction "PS_DDR_DQ13_502_N24") (pintype "bidirectional"))
    )
    (net (code "42") (name "/DDR_DQ14") (class "Default")
      (node (ref "IC37B") (pin "B8") (pinfunction "DQ14_B8") (pintype "bidirectional"))
      (node (ref "IC6") (pin "M24") (pinfunction "PS_DDR_DQ14_502_M24") (pintype "bidirectional"))
    )
    (net (code "43") (name "/DDR_DQ15") (class "Default")
      (node (ref "IC37B") (pin "A3") (pinfunction "DQ15_A3") (pintype "bidirectional"))
      (node (ref "IC6") (pin "N23") (pinfunction "PS_DDR_DQ15_502_N23") (pintype "bidirectional"))
    )
    (net (code "44") (name "/DDR_DQ16") (class "Default")
      (node (ref "IC37A") (pin "E3") (pinfunction "DQ0_E3") (pintype "bidirectional"))
      (node (ref "IC6") (pin "R26") (pinfunction "PS_DDR_DQ16_502_R26") (pintype "bidirectional"))
    )
    (net (code "45") (name "/DDR_DQ17") (class "Default")
      (node (ref "IC37A") (pin "F7") (pinfunction "DQ1_F7") (pintype "bidirectional"))
      (node (ref "IC6") (pin "P24") (pinfunction "PS_DDR_DQ17_502_P24") (pintype "bidirectional"))
    )
    (net (code "46") (name "/DDR_DQ18") (class "Default")
      (node (ref "IC37A") (pin "F2") (pinfunction "DQ2_F2") (pintype "bidirectional"))
      (node (ref "IC6") (pin "N26") (pinfunction "PS_DDR_DQ18_502_N26") (pintype "bidirectional"))
    )
    (net (code "47") (name "/DDR_DQ19") (class "Default")
      (node (ref "IC37A") (pin "F8") (pinfunction "DQ3_F8") (pintype "bidirectional"))
      (node (ref "IC6") (pin "P23") (pinfunction "PS_DDR_DQ19_502_P23") (pintype "bidirectional"))
    )
    (net (code "48") (name "/DDR_DQ20") (class "Default")
      (node (ref "IC37A") (pin "H3") (pinfunction "DQ4_H3") (pintype "bidirectional"))
      (node (ref "IC6") (pin "T24") (pinfunction "PS_DDR_DQ20_502_T24") (pintype "bidirectional"))
    )
    (net (code "49") (name "/DDR_DQ21") (class "Default")
      (node (ref "IC37A") (pin "H8") (pinfunction "DQ5_H8") (pintype "bidirectional"))
      (node (ref "IC6") (pin "T25") (pinfunction "PS_DDR_DQ21_502_T25") (pintype "bidirectional"))
    )
    (net (code "50") (name "/DDR_DQ22") (class "Default")
      (node (ref "IC37A") (pin "G2") (pinfunction "DQ6_G2") (pintype "bidirectional"))
      (node (ref "IC6") (pin "T23") (pinfunction "PS_DDR_DQ22_502_T23") (pintype "bidirectional"))
    )
    (net (code "51") (name "/DDR_DQ23") (class "Default")
      (node (ref "IC37A") (pin "H7") (pinfunction "DQ7_H7") (pintype "bidirectional"))
      (node (ref "IC6") (pin "R23") (pinfunction "PS_DDR_DQ23_502_R23") (pintype "bidirectional"))
    )
    (net (code "52") (name "/DDR_DQ24") (class "Default")
      (node (ref "IC37A") (pin "D7") (pinfunction "DQ8_D7") (pintype "bidirectional"))
      (node (ref "IC6") (pin "V24") (pinfunction "PS_DDR_DQ24_502_V24") (pintype "bidirectional"))
    )
    (net (code "53") (name "/DDR_DQ25") (class "Default")
      (node (ref "IC37A") (pin "C3") (pinfunction "DQ9_C3") (pintype "bidirectional"))
      (node (ref "IC6") (pin "U26") (pinfunction "PS_DDR_DQ25_502_U26") (pintype "bidirectional"))
    )
    (net (code "54") (name "/DDR_DQ26") (class "Default")
      (node (ref "IC37A") (pin "C8") (pinfunction "DQ10_C8") (pintype "bidirectional"))
      (node (ref "IC6") (pin "U24") (pinfunction "PS_DDR_DQ26_502_U24") (pintype "bidirectional"))
    )
    (net (code "55") (name "/DDR_DQ27") (class "Default")
      (node (ref "IC37A") (pin "C2") (pinfunction "DQ11_C2") (pintype "bidirectional"))
      (node (ref "IC6") (pin "U25") (pinfunction "PS_DDR_DQ27_502_U25") (pintype "bidirectional"))
    )
    (net (code "56") (name "/DDR_DQ28") (class "Default")
      (node (ref "IC37A") (pin "A7") (pinfunction "DQ12_A7") (pintype "bidirectional"))
      (node (ref "IC6") (pin "W26") (pinfunction "PS_DDR_DQ28_502_W26") (pintype "bidirectional"))
    )
    (net (code "57") (name "/DDR_DQ29") (class "Default")
      (node (ref "IC37A") (pin "A2") (pinfunction "DQ13_A2") (pintype "bidirectional"))
      (node (ref "IC6") (pin "Y25") (pinfunction "PS_DDR_DQ29_502_Y25") (pintype "bidirectional"))
    )
    (net (code "58") (name "/DDR_DQ30") (class "Default")
      (node (ref "IC37A") (pin "B8") (pinfunction "DQ14_B8") (pintype "bidirectional"))
      (node (ref "IC6") (pin "Y26") (pinfunction "PS_DDR_DQ30_502_Y26") (pintype "bidirectional"))
    )
    (net (code "59") (name "/DDR_DQ31") (class "Default")
      (node (ref "IC37A") (pin "A3") (pinfunction "DQ15_A3") (pintype "bidirectional"))
      (node (ref "IC6") (pin "W23") (pinfunction "PS_DDR_DQ31_502_W23") (pintype "bidirectional"))
    )
    (net (code "60") (name "/DDR_DQS0_N") (class "Default")
      (node (ref "IC37B") (pin "G3") (pinfunction "~{LDQS}_G3") (pintype "bidirectional"))
      (node (ref "IC6") (pin "G25") (pinfunction "PS_DDR_DQS_N0_502_G25") (pintype "bidirectional"))
    )
    (net (code "61") (name "/DDR_DQS0_P") (class "Default")
      (node (ref "IC37B") (pin "F3") (pinfunction "LDQS_F3") (pintype "bidirectional"))
      (node (ref "IC6") (pin "H24") (pinfunction "PS_DDR_DQS_P0_502_H24") (pintype "bidirectional"))
    )
    (net (code "62") (name "/DDR_DQS1_N") (class "Default")
      (node (ref "IC37B") (pin "B7") (pinfunction "~{UDQS}_B7") (pintype "bidirectional"))
      (node (ref "IC6") (pin "L25") (pinfunction "PS_DDR_DQS_N1_502_L25") (pintype "bidirectional"))
    )
    (net (code "63") (name "/DDR_DQS1_P") (class "Default")
      (node (ref "IC37B") (pin "C7") (pinfunction "UDQS_C7") (pintype "bidirectional"))
      (node (ref "IC6") (pin "L24") (pinfunction "PS_DDR_DQS_P1_502_L24") (pintype "bidirectional"))
    )
    (net (code "64") (name "/DDR_DQS2_N") (class "Default")
      (node (ref "IC37A") (pin "G3") (pinfunction "~{LDQS}_G3") (pintype "bidirectional"))
      (node (ref "IC6") (pin "R25") (pinfunction "PS_DDR_DQS_N2_502_R25") (pintype "bidirectional"))
    )
    (net (code "65") (name "/DDR_DQS2_P") (class "Default")
      (node (ref "IC37A") (pin "F3") (pinfunction "LDQS_F3") (pintype "bidirectional"))
      (node (ref "IC6") (pin "P25") (pinfunction "PS_DDR_DQS_P2_502_P25") (pintype "bidirectional"))
    )
    (net (code "66") (name "/DDR_DQS3_N") (class "Default")
      (node (ref "IC37A") (pin "B7") (pinfunction "~{UDQS}_B7") (pintype "bidirectional"))
      (node (ref "IC6") (pin "W25") (pinfunction "PS_DDR_DQS_N3_502_W25") (pintype "bidirectional"))
    )
    (net (code "67") (name "/DDR_DQS3_P") (class "Default")
      (node (ref "IC37A") (pin "C7") (pinfunction "UDQS_C7") (pintype "bidirectional"))
      (node (ref "IC6") (pin "W24") (pinfunction "PS_DDR_DQS_P3_502_W24") (pintype "bidirectional"))
    )
    (net (code "68") (name "/DDR_DRST") (class "Default")
      (node (ref "IC37A") (pin "T2") (pinfunction "~{RESET}_T2") (pintype "input"))
      (node (ref "IC37B") (pin "T2") (pinfunction "~{RESET}_T2") (pintype "input"))
      (node (ref "IC6") (pin "H22") (pinfunction "PS_DDR_DRST_B_502_H22") (pintype "output"))
      (node (ref "R335") (pin "1") (pinfunction "1_1") (pintype "passive"))
    )
    (net (code "69") (name "/DDR_ODT") (class "Default")
      (node (ref "IC37A") (pin "K1") (pinfunction "ODT_K1") (pintype "input"))
      (node (ref "IC37B") (pin "K1") (pinfunction "ODT_K1") (pintype "input"))
      (node (ref "IC6") (pin "Y22") (pinfunction "PS_DDR_ODT_502_Y22") (pintype "output"))
      (node (ref "R327") (pin "1") (pinfunction "1_1") (pintype "passive"))
    )
    (net (code "70") (name "/DDR_RAS") (class "Default")
      (node (ref "IC37A") (pin "J3") (pinfunction "~{RAS}_J3") (pintype "input"))
      (node (ref "IC37B") (pin "J3") (pinfunction "~{RAS}_J3") (pintype "input"))
      (node (ref "IC6") (pin "V23") (pinfunction "PS_DDR_RAS_B_502_V23") (pintype "output"))
      (node (ref "R321") (pin "1") (pinfunction "1_1") (pintype "passive"))
    )
    (net (code "71") (name "/DDR_WE") (class "Default")
      (node (ref "IC37A") (pin "L3") (pinfunction "~{WE}_L3") (pintype "input"))
      (node (ref "IC37B") (pin "L3") (pinfunction "~{WE}_L3") (pintype "input"))
      (node (ref "IC6") (pin "V22") (pinfunction "PS_DDR_WE_B_502_V22") (pintype "output"))
      (node (ref "R323") (pin "1") (pinfunction "1_1") (pintype "passive"))
    )
    (net (code "72") (name "GND") (class "Default")
      (node (ref "C100") (pin "1") (pinfunction "1_1") (pintype "passive"))
      (node (ref "C101") (pin "1") (pinfunction "1_1") (pintype "passive"))
      (node (ref "C102") (pin "1") (pinfunction "1_1") (pintype "passive"))
      (node (ref "C103") (pin "1") (pinfunction "1_1") (pintype "passive"))
      (node (ref "C104") (pin "1") (pinfunction "1_1") (pintype "passive"))
      (node (ref "C105") (pin "1") (pinfunction "1_1") (pintype "passive"))
      (node (ref "C106") (pin "1") (pinfunction "1_1") (pintype "passive"))
      (node (ref "C107") (pin "1") (pinfunction "1_1") (pintype "passive"))
      (node (ref "C108") (pin "1") (pinfunction "1_1") (pintype "passive"))
      (node (ref "C109") (pin "1") (pinfunction "1_1") (pintype "passive"))
      (node (ref "C110") (pin "1") (pinfunction "1_1") (pintype "passive"))
      (node (ref "C111") (pin "1") (pinfunction "1_1") (pintype "passive"))
      (node (ref "C112") (pin "1") (pinfunction "1_1") (pintype "passive"))
      (node (ref "C77") (pin "1") (pinfunction "1_1") (pintype "passive"))
      (node (ref "C78") (pin "1") (pinfunction "1_1") (pintype "passive"))
      (node (ref "C79") (pin "1") (pinfunction "1_1") (pintype "passive"))
      (node (ref "C80") (pin "1") (pinfunction "1_1") (pintype "passive"))
      (node (ref "C81") (pin "1") (pinfunction "1_1") (pintype "passive"))
      (node (ref "C82") (pin "1") (pinfunction "1_1") (pintype "passive"))
      (node (ref "C83") (pin "1") (pinfunction "1_1") (pintype "passive"))
      (node (ref "C84") (pin "1") (pinfunction "1_1") (pintype "passive"))
      (node (ref "C85") (pin "1") (pinfunction "1_1") (pintype "passive"))
      (node (ref "C86") (pin "1") (pinfunction "1_1") (pintype "passive"))
      (node (ref "C87") (pin "1") (pinfunction "1_1") (pintype "passive"))
      (node (ref "C88") (pin "1") (pinfunction "1_1") (pintype "passive"))
      (node (ref "C89") (pin "1") (pinfunction "1_1") (pintype "passive"))
      (node (ref "C90") (pin "1") (pinfunction "1_1") (pintype "passive"))
      (node (ref "C91") (pin "1") (pinfunction "1_1") (pintype "passive"))
      (node (ref "C92") (pin "1") (pinfunction "1_1") (pintype "passive"))
      (node (ref "C93") (pin "1") (pinfunction "1_1") (pintype "passive"))
      (node (ref "C94") (pin "1") (pinfunction "1_1") (pintype "passive"))
      (node (ref "C95") (pin "1") (pinfunction "1_1") (pintype "passive"))
      (node (ref "C96") (pin "1") (pinfunction "1_1") (pintype "passive"))
      (node (ref "C97") (pin "1") (pinfunction "1_1") (pintype "passive"))
      (node (ref "C98") (pin "1") (pinfunction "1_1") (pintype "passive"))
      (node (ref "C99") (pin "1") (pinfunction "1_1") (pintype "passive"))
      (node (ref "IC37A") (pin "A9") (pinfunction "VSS_A9") (pintype "power_in"))
      (node (ref "IC37A") (pin "B1") (pinfunction "VSSQ_B1") (pintype "power_in"))
      (node (ref "IC37A") (pin "B3") (pinfunction "VSS_B3") (pintype "power_in"))
      (node (ref "IC37A") (pin "B9") (pinfunction "VSSQ_B9") (pintype "power_in"))
      (node (ref "IC37A") (pin "D1") (pinfunction "VSSQ_D1") (pintype "power_in"))
      (node (ref "IC37A") (pin "D8") (pinfunction "VSSQ_D8") (pintype "power_in"))
      (node (ref "IC37A") (pin "E1") (pinfunction "VSS_E1") (pintype "power_in"))
      (node (ref "IC37A") (pin "E2") (pinfunction "VSSQ_E2") (pintype "power_in"))
      (node (ref "IC37A") (pin "E8") (pinfunction "VSSQ_E8") (pintype "power_in"))
      (node (ref "IC37A") (pin "F9") (pinfunction "VSSQ_F9") (pintype "power_in"))
      (node (ref "IC37A") (pin "G1") (pinfunction "VSSQ_G1") (pintype "power_in"))
      (node (ref "IC37A") (pin "G8") (pinfunction "VSS_G8") (pintype "power_in"))
      (node (ref "IC37A") (pin "G9") (pinfunction "VSSQ_G9") (pintype "power_in"))
      (node (ref "IC37A") (pin "J2") (pinfunction "VSS_J2") (pintype "power_in"))
      (node (ref "IC37A") (pin "J8") (pinfunction "VSS_J8") (pintype "power_in"))
      (node (ref "IC37A") (pin "M1") (pinfunction "VSS_M1") (pintype "power_in"))
      (node (ref "IC37A") (pin "M9") (pinfunction "VSS_M9") (pintype "power_in"))
      (node (ref "IC37A") (pin "P1") (pinfunction "VSS_P1") (pintype "power_in"))
      (node (ref "IC37A") (pin "P9") (pinfunction "VSS_P9") (pintype "power_in"))
      (node (ref "IC37A") (pin "T1") (pinfunction "VSS_T1") (pintype "power_in"))
      (node (ref "IC37A") (pin "T9") (pinfunction "VSS_T9") (pintype "power_in"))
      (node (ref "IC37B") (pin "A9") (pinfunction "VSS_A9") (pintype "power_in"))
      (node (ref "IC37B") (pin "B1") (pinfunction "VSSQ_B1") (pintype "power_in"))
      (node (ref "IC37B") (pin "B3") (pinfunction "VSS_B3") (pintype "power_in"))
      (node (ref "IC37B") (pin "B9") (pinfunction "VSSQ_B9") (pintype "power_in"))
      (node (ref "IC37B") (pin "D1") (pinfunction "VSSQ_D1") (pintype "power_in"))
      (node (ref "IC37B") (pin "D8") (pinfunction "VSSQ_D8") (pintype "power_in"))
      (node (ref "IC37B") (pin "E1") (pinfunction "VSS_E1") (pintype "power_in"))
      (node (ref "IC37B") (pin "E2") (pinfunction "VSSQ_E2") (pintype "power_in"))
      (node (ref "IC37B") (pin "E8") (pinfunction "VSSQ_E8") (pintype "power_in"))
      (node (ref "IC37B") (pin "F9") (pinfunction "VSSQ_F9") (pintype "power_in"))
      (node (ref "IC37B") (pin "G1") (pinfunction "VSSQ_G1") (pintype "power_in"))
      (node (ref "IC37B") (pin "G8") (pinfunction "VSS_G8") (pintype "power_in"))
      (node (ref "IC37B") (pin "G9") (pinfunction "VSSQ_G9") (pintype "power_in"))
      (node (ref "IC37B") (pin "J2") (pinfunction "VSS_J2") (pintype "power_in"))
      (node (ref "IC37B") (pin "J8") (pinfunction "VSS_J8") (pintype "power_in"))
      (node (ref "IC37B") (pin "M1") (pinfunction "VSS_M1") (pintype "power_in"))
      (node (ref "IC37B") (pin "M9") (pinfunction "VSS_M9") (pintype "power_in"))
      (node (ref "IC37B") (pin "P1") (pinfunction "VSS_P1") (pintype "power_in"))
      (node (ref "IC37B") (pin "P9") (pinfunction "VSS_P9") (pintype "power_in"))
      (node (ref "IC37B") (pin "T1") (pinfunction "VSS_T1") (pintype "power_in"))
      (node (ref "IC37B") (pin "T9") (pinfunction "VSS_T9") (pintype "power_in"))
      (node (ref "R335") (pin "2") (pinfunction "2_2") (pintype "passive"))
      (node (ref "R84") (pin "1") (pinfunction "1_1") (pintype "passive"))
      (node (ref "R85") (pin "1") (pinfunction "1_1") (pintype "passive"))
      (node (ref "R90") (pin "2") (pinfunction "2_2") (pintype "passive"))
    )
    (net (code "73") (name "Net-(IC6H-PS_DDR_VRN_502)") (class "Default")
      (node (ref "IC6") (pin "V21") (pinfunction "PS_DDR_VRN_502_V21") (pintype "output"))
      (node (ref "R109") (pin "1") (pinfunction "1_1") (pintype "passive"))
      (node (ref "R91") (pin "1") (pinfunction "1_1") (pintype "passive"))
    )
    (net (code "74") (name "Net-(IC6H-PS_DDR_VRP_502)") (class "Default")
      (node (ref "IC6") (pin "W21") (pinfunction "PS_DDR_VRP_502_W21") (pintype "output"))
      (node (ref "R90") (pin "1") (pinfunction "1_1") (pintype "passive"))
    )
    (net (code "75") (name "Net-(IC37A-ZQ)") (class "Default")
      (node (ref "IC37A") (pin "L8") (pinfunction "ZQ_L8") (pintype "input"))
      (node (ref "R84") (pin "2") (pinfunction "2_2") (pintype "passive"))
    )
    (net (code "76") (name "Net-(IC37B-ZQ)") (class "Default")
      (node (ref "IC37B") (pin "L8") (pinfunction "ZQ_L8") (pintype "input"))
      (node (ref "R85") (pin "2") (pinfunction "2_2") (pintype "passive"))
    )
    (net (code "77") (name "VCCDDR") (class "Default")
      (node (ref "C100") (pin "2") (pinfunction "2_2") (pintype "passive"))
      (node (ref "C101") (pin "2") (pinfunction "2_2") (pintype "passive"))
      (node (ref "C102") (pin "2") (pinfunction "2_2") (pintype "passive"))
      (node (ref "C103") (pin "2") (pinfunction "2_2") (pintype "passive"))
      (node (ref "C104") (pin "2") (pinfunction "2_2") (pintype "passive"))
      (node (ref "C83") (pin "2") (pinfunction "2_2") (pintype "passive"))
      (node (ref "C84") (pin "2") (pinfunction "2_2") (pintype "passive"))
      (node (ref "C85") (pin "2") (pinfunction "2_2") (pintype "passive"))
      (node (ref "C86") (pin "2") (pinfunction "2_2") (pintype "passive"))
      (node (ref "C87") (pin "2") (pinfunction "2_2") (pintype "passive"))
      (node (ref "C88") (pin "2") (pinfunction "2_2") (pintype "passive"))
      (node (ref "C89") (pin "2") (pinfunction "2_2") (pintype "passive"))
      (node (ref "C90") (pin "2") (pinfunction "2_2") (pintype "passive"))
      (node (ref "C91") (pin "2") (pinfunction "2_2") (pintype "passive"))
      (node (ref "C92") (pin "2") (pinfunction "2_2") (pintype "passive"))
      (node (ref "C93") (pin "2") (pinfunction "2_2") (pintype "passive"))
      (node (ref "C94") (pin "2") (pinfunction "2_2") (pintype "passive"))
      (node (ref "C95") (pin "2") (pinfunction "2_2") (pintype "passive"))
      (node (ref "C96") (pin "2") (pinfunction "2_2") (pintype "passive"))
      (node (ref "C97") (pin "2") (pinfunction "2_2") (pintype "passive"))
      (node (ref "C98") (pin "2") (pinfunction "2_2") (pintype "passive"))
      (node (ref "C99") (pin "2") (pinfunction "2_2") (pintype "passive"))
      (node (ref "IC37A") (pin "A1") (pinfunction "VDDQ_A1") (pintype "power_in"))
      (node (ref "IC37A") (pin "A8") (pinfunction "VDDQ_A8") (pintype "power_in"))
      (node (ref "IC37A") (pin "B2") (pinfunction "VDD_B2") (pintype "power_in"))
      (node (ref "IC37A") (pin "C1") (pinfunction "VDDQ_C1") (pintype "power_in"))
      (node (ref "IC37A") (pin "C9") (pinfunction "VDDQ_C9") (pintype "power_in"))
      (node (ref "IC37A") (pin "D2") (pinfunction "VDDQ_D2") (pintype "power_in"))
      (node (ref "IC37A") (pin "D9") (pinfunction "VDD_D9") (pintype "power_in"))
      (node (ref "IC37A") (pin "E9") (pinfunction "VDDQ_E9") (pintype "power_in"))
      (node (ref "IC37A") (pin "F1") (pinfunction "VDDQ_F1") (pintype "power_in"))
      (node (ref "IC37A") (pin "G7") (pinfunction "VDD_G7") (pintype "power_in"))
      (node (ref "IC37A") (pin "H2") (pinfunction "VDDQ_H2") (pintype "power_in"))
      (node (ref "IC37A") (pin "H9") (pinfunction "VDDQ_H9") (pintype "power_in"))
      (node (ref "IC37A") (pin "K2") (pinfunction "VDD_K2") (pintype "power_in"))
      (node (ref "IC37A") (pin "K8") (pinfunction "VDD_K8") (pintype "power_in"))
      (node (ref "IC37A") (pin "N1") (pinfunction "VDD_N1") (pintype "power_in"))
      (node (ref "IC37A") (pin "N9") (pinfunction "VDD_N9") (pintype "power_in"))
      (node (ref "IC37A") (pin "R1") (pinfunction "VDD_R1") (pintype "power_in"))
      (node (ref "IC37A") (pin "R9") (pinfunction "VDD_R9") (pintype "power_in"))
      (node (ref "IC37B") (pin "A1") (pinfunction "VDDQ_A1") (pintype "power_in"))
      (node (ref "IC37B") (pin "A8") (pinfunction "VDDQ_A8") (pintype "power_in"))
      (node (ref "IC37B") (pin "B2") (pinfunction "VDD_B2") (pintype "power_in"))
      (node (ref "IC37B") (pin "C1") (pinfunction "VDDQ_C1") (pintype "power_in"))
      (node (ref "IC37B") (pin "C9") (pinfunction "VDDQ_C9") (pintype "power_in"))
      (node (ref "IC37B") (pin "D2") (pinfunction "VDDQ_D2") (pintype "power_in"))
      (node (ref "IC37B") (pin "D9") (pinfunction "VDD_D9") (pintype "power_in"))
      (node (ref "IC37B") (pin "E9") (pinfunction "VDDQ_E9") (pintype "power_in"))
      (node (ref "IC37B") (pin "F1") (pinfunction "VDDQ_F1") (pintype "power_in"))
      (node (ref "IC37B") (pin "G7") (pinfunction "VDD_G7") (pintype "power_in"))
      (node (ref "IC37B") (pin "H2") (pinfunction "VDDQ_H2") (pintype "power_in"))
      (node (ref "IC37B") (pin "H9") (pinfunction "VDDQ_H9") (pintype "power_in"))
      (node (ref "IC37B") (pin "K2") (pinfunction "VDD_K2") (pintype "power_in"))
      (node (ref "IC37B") (pin "K8") (pinfunction "VDD_K8") (pintype "power_in"))
      (node (ref "IC37B") (pin "N1") (pinfunction "VDD_N1") (pintype "power_in"))
      (node (ref "IC37B") (pin "N9") (pinfunction "VDD_N9") (pintype "power_in"))
      (node (ref "IC37B") (pin "R1") (pinfunction "VDD_R1") (pintype "power_in"))
      (node (ref "IC37B") (pin "R9") (pinfunction "VDD_R9") (pintype "power_in"))
      (node (ref "R109") (pin "2") (pinfunction "2_2") (pintype "passive"))
    )
    (net (code "78") (name "VREF_DDR") (class "Default")
      (node (ref "C77") (pin "2") (pinfunction "2_2") (pintype "passive"))
      (node (ref "C78") (pin "2") (pinfunction "2_2") (pintype "passive"))
      (node (ref "C79") (pin "2") (pinfunction "2_2") (pintype "passive"))
      (node (ref "C80") (pin "2") (pinfunction "2_2") (pintype "passive"))
      (node (ref "C81") (pin "2") (pinfunction "2_2") (pintype "passive"))
      (node (ref "C82") (pin "2") (pinfunction "2_2") (pintype "passive"))
      (node (ref "IC37A") (pin "H1") (pinfunction "VREFDQ_H1") (pintype "power_in"))
      (node (ref "IC37A") (pin "M8") (pinfunction "VREFCA_M8") (pintype "power_in"))
      (node (ref "IC37B") (pin "H1") (pinfunction "VREFDQ_H1") (pintype "power_in"))
      (node (ref "IC37B") (pin "M8") (pinfunction "VREFCA_M8") (pintype "power_in"))
      (node (ref "IC6") (pin "K21") (pinfunction "PS_DDR_VREF0_502_K21") (pintype "input"))
      (node (ref "IC6") (pin "M21") (pinfunction "PS_DDR_VREF1_502_M21") (pintype "input"))
    )
    (net (code "79") (name "VTT_DDR") (class "Default")
      (node (ref "C105") (pin "2") (pinfunction "2_2") (pintype "passive"))
      (node (ref "C106") (pin "2") (pinfunction "2_2") (pintype "passive"))
      (node (ref "C107") (pin "2") (pinfunction "2_2") (pintype "passive"))
      (node (ref "C108") (pin "2") (pinfunction "2_2") (pintype "passive"))
      (node (ref "C109") (pin "2") (pinfunction "2_2") (pintype "passive"))
      (node (ref "C110") (pin "2") (pinfunction "2_2") (pintype "passive"))
      (node (ref "C111") (pin "2") (pinfunction "2_2") (pintype "passive"))
      (node (ref "C112") (pin "2") (pinfunction "2_2") (pintype "passive"))
      (node (ref "R292") (pin "2") (pinfunction "2_2") (pintype "passive"))
      (node (ref "R293") (pin "2") (pinfunction "2_2") (pintype "passive"))
      (node (ref "R294") (pin "2") (pinfunction "2_2") (pintype "passive"))
      (node (ref "R295") (pin "2") (pinfunction "2_2") (pintype "passive"))
      (node (ref "R296") (pin "2") (pinfunction "2_2") (pintype "passive"))
      (node (ref "R299") (pin "2") (pinfunction "2_2") (pintype "passive"))
      (node (ref "R311") (pin "2") (pinfunction "2_2") (pintype "passive"))
      (node (ref "R312") (pin "2") (pinfunction "2_2") (pintype "passive"))
      (node (ref "R313") (pin "2") (pinfunction "2_2") (pintype "passive"))
      (node (ref "R314") (pin "2") (pinfunction "2_2") (pintype "passive"))
      (node (ref "R315") (pin "2") (pinfunction "2_2") (pintype "passive"))
      (node (ref "R316") (pin "2") (pinfunction "2_2") (pintype "passive"))
      (node (ref "R317") (pin "2") (pinfunction "2_2") (pintype "passive"))
      (node (ref "R318") (pin "2") (pinfunction "2_2") (pintype "passive"))
      (node (ref "R319") (pin "2") (pinfunction "2_2") (pintype "passive"))
      (node (ref "R320") (pin "2") (pinfunction "2_2") (pintype "passive"))
      (node (ref "R321") (pin "2") (pinfunction "2_2") (pintype "passive"))
      (node (ref "R322") (pin "2") (pinfunction "2_2") (pintype "passive"))
      (node (ref "R323") (pin "2") (pinfunction "2_2") (pintype "passive"))
      (node (ref "R324") (pin "2") (pinfunction "2_2") (pintype "passive"))
      (node (ref "R325") (pin "2") (pinfunction "2_2") (pintype "passive"))
      (node (ref "R326") (pin "2") (pinfunction "2_2") (pintype "passive"))
      (node (ref "R327") (pin "2") (pinfunction "2_2") (pintype "passive"))
      (node (ref "R328") (pin "2") (pinfunction "2_2") (pintype "passive"))
      (node (ref "R91") (pin "2") (pinfunction "2_2") (pintype "passive"))
    )
    (net (code "80") (name "unconnected-(IC37A-NC-PadJ1)") (class "Default")
      (node (ref "IC37A") (pin "J1") (pinfunction "NC_J1") (pintype "passive+no_connect"))
    )
    (net (code "81") (name "unconnected-(IC37A-NC-PadJ9)") (class "Default")
      (node (ref "IC37A") (pin "J9") (pinfunction "NC_J9") (pintype "passive+no_connect"))
    )
    (net (code "82") (name "unconnected-(IC37A-NC-PadL1)") (class "Default")
      (node (ref "IC37A") (pin "L1") (pinfunction "NC_L1") (pintype "passive+no_connect"))
    )
    (net (code "83") (name "unconnected-(IC37A-NC-PadL9)") (class "Default")
      (node (ref "IC37A") (pin "L9") (pinfunction "NC_L9") (pintype "passive+no_connect"))
    )
    (net (code "84") (name "unconnected-(IC37A-NC-PadM7)") (class "Default")
      (node (ref "IC37A") (pin "M7") (pinfunction "NC_M7") (pintype "passive+no_connect"))
    )
    (net (code "85") (name "unconnected-(IC37B-NC-PadJ1)") (class "Default")
      (node (ref "IC37B") (pin "J1") (pinfunction "NC_J1") (pintype "passive+no_connect"))
    )
    (net (code "86") (name "unconnected-(IC37B-NC-PadJ9)") (class "Default")
      (node (ref "IC37B") (pin "J9") (pinfunction "NC_J9") (pintype "passive+no_connect"))
    )
    (net (code "87") (name "unconnected-(IC37B-NC-PadL1)") (class "Default")
      (node (ref "IC37B") (pin "L1") (pinfunction "NC_L1") (pintype "passive+no_connect"))
    )
    (net (code "88") (name "unconnected-(IC37B-NC-PadL9)") (class "Default")
      (node (ref "IC37B") (pin "L9") (pinfunction "NC_L9") (pintype "passive+no_connect"))
    )
    (net (code "89") (name "unconnected-(IC37B-NC-PadM7)") (class "Default")
      (node (ref "IC37B") (pin "M7") (pinfunction "NC_M7") (pintype "passive+no_connect"))
    )
  )
)
